# 06_-_MOTOR_DRIVERS.net
KiCad netlist of a schematic drawn in Altium Designer
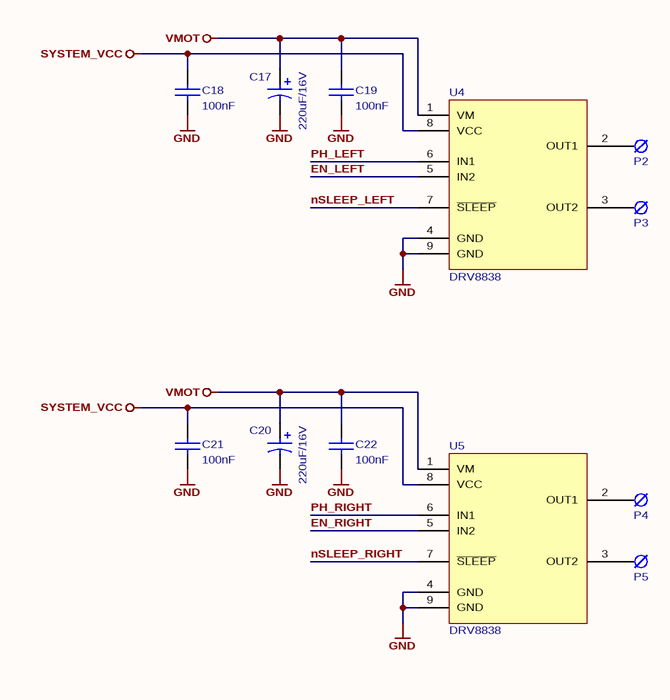
[diagram p0: [06] - MOTOR DRIVERS.SchDoc]

(export (version "E")
  (design (tool "Eeschema 10.0.6"))
  (components
    (comp (ref "C17")
      (value "220uF/16V")
      (footprint "CES_E_8.3x8.3_6.2")
      (description "Polarized Capacitor")
      (libsource (lib "capacitors") (part "Cap Pol"))
    )
    (comp (ref "C18")
      (value "100nF")
      (footprint "C0805")
      (description "Capacitor")
      (libsource (lib "capacitors") (part "Cap"))
    )
    (comp (ref "C19")
      (value "100nF")
      (footprint "C0805")
      (description "Capacitor")
      (libsource (lib "capacitors") (part "Cap"))
    )
    (comp (ref "C20")
      (value "220uF/16V")
      (footprint "CES_E_8.3x8.3_6.2")
      (description "Polarized Capacitor")
      (libsource (lib "capacitors") (part "Cap Pol"))
    )
    (comp (ref "C21")
      (value "100nF")
      (footprint "C0805")
      (description "Capacitor")
      (libsource (lib "capacitors") (part "Cap"))
    )
    (comp (ref "C22")
      (value "100nF")
      (footprint "C0805")
      (description "Capacitor")
      (libsource (lib "capacitors") (part "Cap"))
    )
    (comp (ref "P2")
      (value "CablePAD")
      (footprint "PADTHT1.5x3mm")
      (description "Cable/Wire Soldering PAD")
      (libsource (lib "wire_and_cable_pads") (part "CablePAD"))
    )
    (comp (ref "P3")
      (value "CablePAD")
      (footprint "PADTHT1.5x3mm")
      (description "Cable/Wire Soldering PAD")
      (libsource (lib "wire_and_cable_pads") (part "CablePAD"))
    )
    (comp (ref "P4")
      (value "CablePAD")
      (footprint "PADTHT1.5x3mm")
      (description "Cable/Wire Soldering PAD")
      (libsource (lib "wire_and_cable_pads") (part "CablePAD"))
    )
    (comp (ref "P5")
      (value "CablePAD")
      (footprint "PADTHT1.5x3mm")
      (description "Cable/Wire Soldering PAD")
      (libsource (lib "wire_and_cable_pads") (part "CablePAD"))
    )
    (comp (ref "U4")
      (value "DRV8838")
      (footprint "WSON8 (DSG8-1600X900TP)")
      (description "Low-Voltage H-Bridge Driver")
      (libsource (lib "motor_drivers") (part "DRV8838"))
    )
    (comp (ref "U5")
      (value "DRV8838")
      (footprint "WSON8 (DSG8-1600X900TP)")
      (description "Low-Voltage H-Bridge Driver")
      (libsource (lib "motor_drivers") (part "DRV8838"))
    )
  )
  (nets
    (net (code "1") (name "/EN_LEFT") (class "Default")
      (node (ref "U4") (pin "5") (pinfunction "IN2_5") (pintype "passive"))
    )
    (net (code "2") (name "/EN_RIGHT") (class "Default")
      (node (ref "U5") (pin "5") (pinfunction "IN2_5") (pintype "passive"))
    )
    (net (code "3") (name "/PH_LEFT") (class "Default")
      (node (ref "U4") (pin "6") (pinfunction "IN1_6") (pintype "passive"))
    )
    (net (code "4") (name "/PH_RIGHT") (class "Default")
      (node (ref "U5") (pin "6") (pinfunction "IN1_6") (pintype "passive"))
    )
    (net (code "5") (name "/nSLEEP_LEFT") (class "Default")
      (node (ref "U4") (pin "7") (pinfunction "~{SLEEP}_7") (pintype "passive"))
    )
    (net (code "6") (name "/nSLEEP_RIGHT") (class "Default")
      (node (ref "U5") (pin "7") (pinfunction "~{SLEEP}_7") (pintype "passive"))
    )
    (net (code "7") (name "GND") (class "Default")
      (node (ref "C17") (pin "2") (pinfunction "2_2") (pintype "passive"))
      (node (ref "C18") (pin "1") (pinfunction "1_1") (pintype "passive"))
      (node (ref "C19") (pin "1") (pinfunction "1_1") (pintype "passive"))
      (node (ref "C20") (pin "2") (pinfunction "2_2") (pintype "passive"))
      (node (ref "C21") (pin "1") (pinfunction "1_1") (pintype "passive"))
      (node (ref "C22") (pin "1") (pinfunction "1_1") (pintype "passive"))
      (node (ref "U4") (pin "4") (pinfunction "GND_4") (pintype "passive"))
      (node (ref "U4") (pin "9") (pinfunction "GND_9") (pintype "passive"))
      (node (ref "U5") (pin "4") (pinfunction "GND_4") (pintype "passive"))
      (node (ref "U5") (pin "9") (pinfunction "GND_9") (pintype "passive"))
    )
    (net (code "8") (name "Net-(U4-OUT1)") (class "Default")
      (node (ref "P2") (pin "0") (pinfunction "0_0") (pintype "passive"))
      (node (ref "U4") (pin "2") (pinfunction "OUT1_2") (pintype "passive"))
    )
    (net (code "9") (name "Net-(U4-OUT2)") (class "Default")
      (node (ref "P3") (pin "0") (pinfunction "0_0") (pintype "passive"))
      (node (ref "U4") (pin "3") (pinfunction "OUT2_3") (pintype "passive"))
    )
    (net (code "10") (name "Net-(U5-OUT1)") (class "Default")
      (node (ref "P4") (pin "0") (pinfunction "0_0") (pintype "passive"))
      (node (ref "U5") (pin "2") (pinfunction "OUT1_2") (pintype "passive"))
    )
    (net (code "11") (name "Net-(U5-OUT2)") (class "Default")
      (node (ref "P5") (pin "0") (pinfunction "0_0") (pintype "passive"))
      (node (ref "U5") (pin "3") (pinfunction "OUT2_3") (pintype "passive"))
    )
    (net (code "12") (name "SYSTEM_VCC") (class "Default")
      (node (ref "C18") (pin "2") (pinfunction "2_2") (pintype "passive"))
      (node (ref "C21") (pin "2") (pinfunction "2_2") (pintype "passive"))
      (node (ref "U4") (pin "8") (pinfunction "VCC_8") (pintype "passive"))
      (node (ref "U5") (pin "8") (pinfunction "VCC_8") (pintype "passive"))
    )
    (net (code "13") (name "VMOT") (class "Default")
      (node (ref "C17") (pin "1") (pinfunction "1_1") (pintype "passive"))
      (node (ref "C19") (pin "2") (pinfunction "2_2") (pintype "passive"))
      (node (ref "C20") (pin "1") (pinfunction "1_1") (pintype "passive"))
      (node (ref "C22") (pin "2") (pinfunction "2_2") (pintype "passive"))
      (node (ref "U4") (pin "1") (pinfunction "VM_1") (pintype "passive"))
      (node (ref "U5") (pin "1") (pinfunction "VM_1") (pintype "passive"))
    )
  )
)
